# schematic.net
KiCad netlist of a schematic drawn in EasyEDA
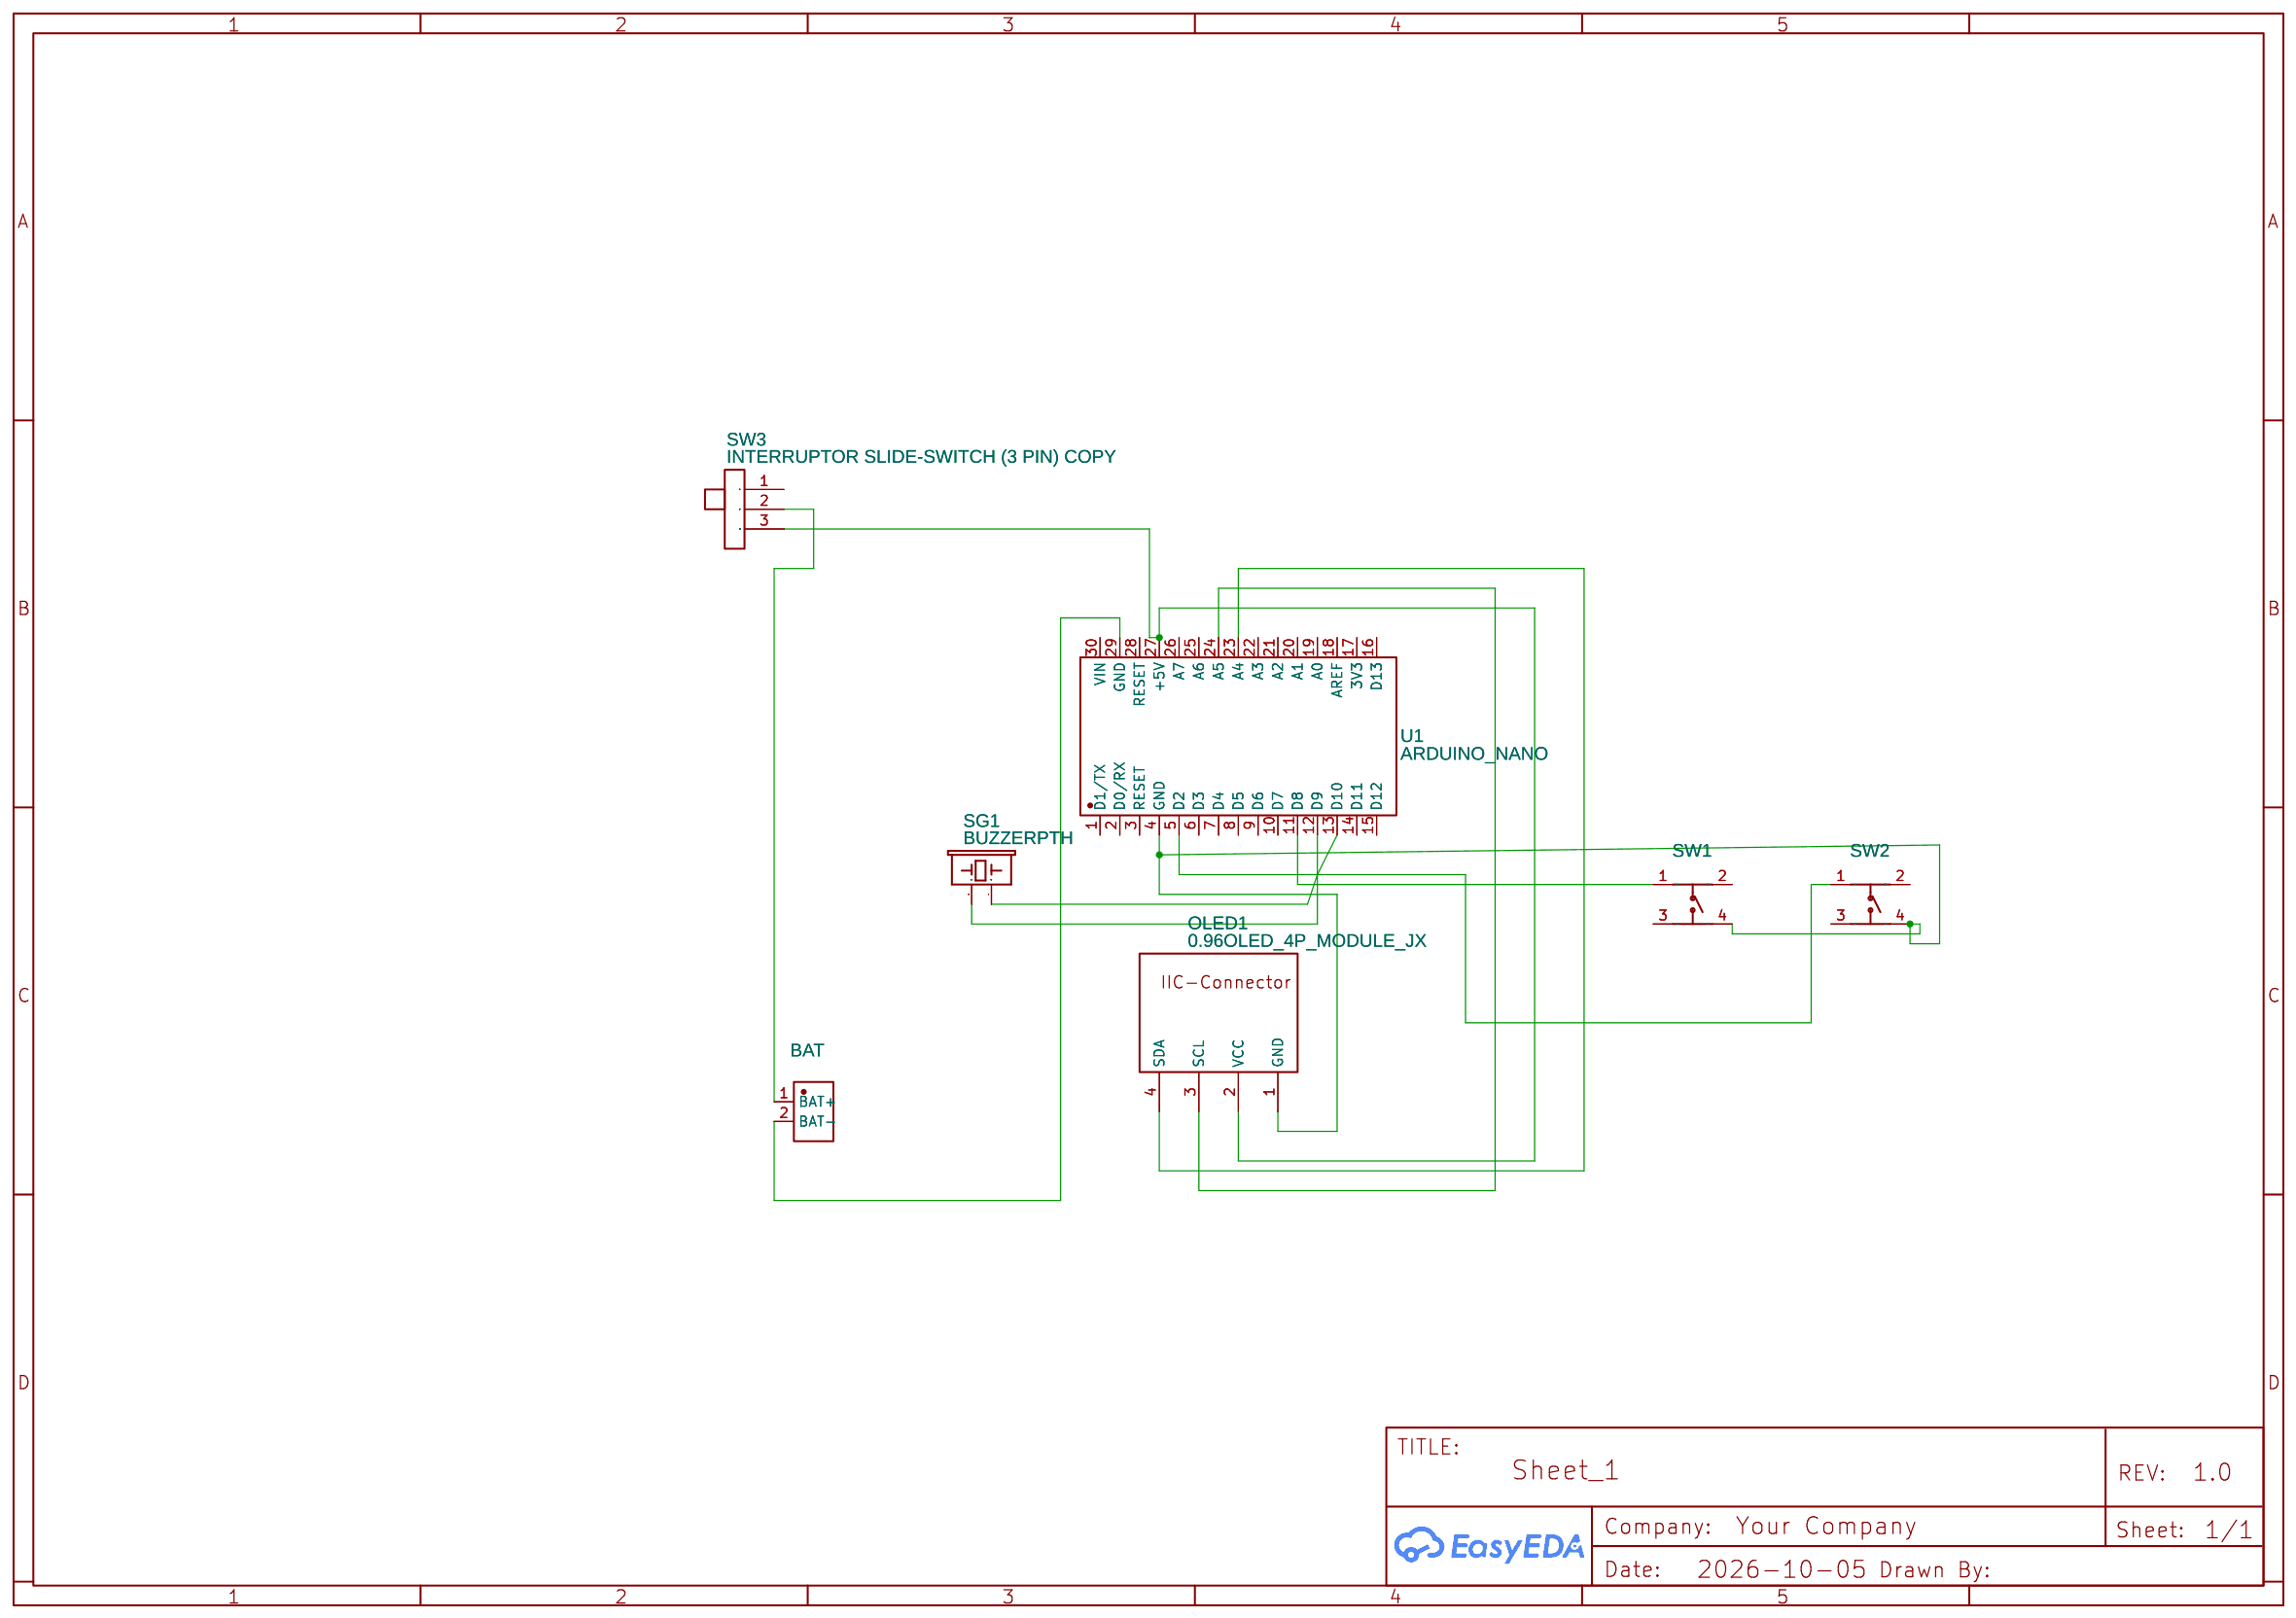
[diagram p0: schematic sheet]

(export (version "E")
  (design (tool "Eeschema 10.0.6"))
  (components
    (comp (ref "BAT")
      (value "880-70-002-10-001101")
      (fields (field (name "Manufacturer") "Preci-Dip"))
      (libsource (lib "") (part "880-70-002-10-001101"))
    )
    (comp (ref "OLED1") (value "0.96OLED_4P_MODULE_JX") (libsource (lib "") (part "0.96OLED_4P_MODULE_JX")))
    (comp (ref "SG1") (value "BUZZERPTH") (libsource (lib "") (part "BUZZERPTH")))
    (comp (ref "SW1")
      (value "SW1")
      (fields (field (name "Manufacturer Part") "Buttontact-6x6mm"))
      (libsource (lib "") (part "BUTTONTACT-6X6MM"))
    )
    (comp (ref "SW2")
      (value "SW2")
      (fields (field (name "Manufacturer Part") "Buttontact-6x6mm"))
      (libsource (lib "") (part "BUTTONTACT-6X6MM"))
    )
    (comp (ref "SW3")
      (value "INTERRUPTOR SLIDE-SWITCH (3 PIN) COPY")
      (fields (field (name "Manufacturer") "A+A Technology Co.,Ltd"))
      (libsource (lib "") (part "INTERRUPTOR SLIDE-SWITCH (3 PIN) COPY"))
    )
    (comp (ref "U1") (value "ARDUINO_NANO") (libsource (lib "") (part "ARDUINO_NANO")))
  )
  (nets
    (net (code "1") (name "Net-(BAT-BAT+)") (class "Default")
      (node (ref "BAT") (pin "1") (pinfunction "BAT+_1") (pintype "unspecified"))
      (node (ref "SW3") (pin "2") (pinfunction "2_2") (pintype "unspecified"))
    )
    (net (code "2") (name "Net-(BAT-BAT-)") (class "Default")
      (node (ref "BAT") (pin "2") (pinfunction "BAT-_2") (pintype "unspecified"))
      (node (ref "U1") (pin "29") (pinfunction "GND_29") (pintype "unspecified"))
    )
    (net (code "3") (name "Net-(OLED1-GND)") (class "Default")
      (node (ref "OLED1") (pin "1") (pinfunction "GND_1") (pintype "unspecified"))
      (node (ref "SW1") (pin "4") (pinfunction "D_4") (pintype "unspecified"))
      (node (ref "SW2") (pin "4") (pinfunction "D_4") (pintype "unspecified"))
      (node (ref "U1") (pin "4") (pinfunction "GND_4") (pintype "unspecified"))
    )
    (net (code "4") (name "Net-(OLED1-SCL)") (class "Default")
      (node (ref "OLED1") (pin "3") (pinfunction "SCL_3") (pintype "unspecified"))
      (node (ref "U1") (pin "24") (pinfunction "A5_24") (pintype "unspecified"))
    )
    (net (code "5") (name "Net-(OLED1-SDA)") (class "Default")
      (node (ref "OLED1") (pin "4") (pinfunction "SDA_4") (pintype "unspecified"))
      (node (ref "U1") (pin "23") (pinfunction "A4_23") (pintype "unspecified"))
    )
    (net (code "6") (name "Net-(OLED1-VCC)") (class "Default")
      (node (ref "OLED1") (pin "2") (pinfunction "VCC_2") (pintype "unspecified"))
      (node (ref "SW3") (pin "3") (pinfunction "3_3") (pintype "unspecified"))
      (node (ref "U1") (pin "27") (pinfunction "+5V_27") (pintype "unspecified"))
    )
    (net (code "7") (name "Net-(SG1-1)") (class "Default")
      (node (ref "SG1") (pin "+") (pinfunction "1_+") (pintype "unspecified"))
      (node (ref "U1") (pin "12") (pinfunction "D9_12") (pintype "unspecified"))
    )
    (net (code "8") (name "Net-(SG1-2)") (class "Default")
      (node (ref "SG1") (pin "-") (pinfunction "2_-") (pintype "unspecified"))
      (node (ref "U1") (pin "13") (pinfunction "D10_13") (pintype "unspecified"))
    )
    (net (code "9") (name "Net-(SW1-A)") (class "Default")
      (node (ref "SW1") (pin "1") (pinfunction "A_1") (pintype "unspecified"))
      (node (ref "U1") (pin "11") (pinfunction "D8_11") (pintype "unspecified"))
    )
    (net (code "10") (name "Net-(SW2-A)") (class "Default")
      (node (ref "SW2") (pin "1") (pinfunction "A_1") (pintype "unspecified"))
      (node (ref "U1") (pin "5") (pinfunction "D2_5") (pintype "unspecified"))
    )
    (net (code "11") (name "unconnected-(SW1-B-Pad2)") (class "Default")
      (node (ref "SW1") (pin "2") (pinfunction "B_2") (pintype "unspecified"))
    )
    (net (code "12") (name "unconnected-(SW1-C-Pad3)") (class "Default")
      (node (ref "SW1") (pin "3") (pinfunction "C_3") (pintype "unspecified"))
    )
    (net (code "13") (name "unconnected-(SW2-B-Pad2)") (class "Default")
      (node (ref "SW2") (pin "2") (pinfunction "B_2") (pintype "unspecified"))
    )
    (net (code "14") (name "unconnected-(SW2-C-Pad3)") (class "Default")
      (node (ref "SW2") (pin "3") (pinfunction "C_3") (pintype "unspecified"))
    )
    (net (code "15") (name "unconnected-(SW3-Pad1)") (class "Default")
      (node (ref "SW3") (pin "1") (pinfunction "1_1") (pintype "unspecified"))
    )
    (net (code "16") (name "unconnected-(U1-3V3-Pad17)") (class "Default")
      (node (ref "U1") (pin "17") (pinfunction "3V3_17") (pintype "unspecified"))
    )
    (net (code "17") (name "unconnected-(U1-A0-Pad19)") (class "Default")
      (node (ref "U1") (pin "19") (pinfunction "A0_19") (pintype "unspecified"))
    )
    (net (code "18") (name "unconnected-(U1-A1-Pad20)") (class "Default")
      (node (ref "U1") (pin "20") (pinfunction "A1_20") (pintype "unspecified"))
    )
    (net (code "19") (name "unconnected-(U1-A2-Pad21)") (class "Default")
      (node (ref "U1") (pin "21") (pinfunction "A2_21") (pintype "unspecified"))
    )
    (net (code "20") (name "unconnected-(U1-A3-Pad22)") (class "Default")
      (node (ref "U1") (pin "22") (pinfunction "A3_22") (pintype "unspecified"))
    )
    (net (code "21") (name "unconnected-(U1-A6-Pad25)") (class "Default")
      (node (ref "U1") (pin "25") (pinfunction "A6_25") (pintype "unspecified"))
    )
    (net (code "22") (name "unconnected-(U1-A7-Pad26)") (class "Default")
      (node (ref "U1") (pin "26") (pinfunction "A7_26") (pintype "unspecified"))
    )
    (net (code "23") (name "unconnected-(U1-AREF-Pad18)") (class "Default")
      (node (ref "U1") (pin "18") (pinfunction "AREF_18") (pintype "unspecified"))
    )
    (net (code "24") (name "unconnected-(U1-D0{slash}RX-Pad2)") (class "Default")
      (node (ref "U1") (pin "2") (pinfunction "D0/RX_2") (pintype "unspecified"))
    )
    (net (code "25") (name "unconnected-(U1-D1{slash}TX-Pad1)") (class "Default")
      (node (ref "U1") (pin "1") (pinfunction "D1/TX_1") (pintype "unspecified"))
    )
    (net (code "26") (name "unconnected-(U1-D3-Pad6)") (class "Default")
      (node (ref "U1") (pin "6") (pinfunction "D3_6") (pintype "unspecified"))
    )
    (net (code "27") (name "unconnected-(U1-D4-Pad7)") (class "Default")
      (node (ref "U1") (pin "7") (pinfunction "D4_7") (pintype "unspecified"))
    )
    (net (code "28") (name "unconnected-(U1-D5-Pad8)") (class "Default")
      (node (ref "U1") (pin "8") (pinfunction "D5_8") (pintype "unspecified"))
    )
    (net (code "29") (name "unconnected-(U1-D6-Pad9)") (class "Default")
      (node (ref "U1") (pin "9") (pinfunction "D6_9") (pintype "unspecified"))
    )
    (net (code "30") (name "unconnected-(U1-D7-Pad10)") (class "Default")
      (node (ref "U1") (pin "10") (pinfunction "D7_10") (pintype "unspecified"))
    )
    (net (code "31") (name "unconnected-(U1-D11-Pad14)") (class "Default")
      (node (ref "U1") (pin "14") (pinfunction "D11_14") (pintype "unspecified"))
    )
    (net (code "32") (name "unconnected-(U1-D12-Pad15)") (class "Default")
      (node (ref "U1") (pin "15") (pinfunction "D12_15") (pintype "unspecified"))
    )
    (net (code "33") (name "unconnected-(U1-D13-Pad16)") (class "Default")
      (node (ref "U1") (pin "16") (pinfunction "D13_16") (pintype "unspecified"))
    )
    (net (code "34") (name "unconnected-(U1-RESET-Pad3)") (class "Default")
      (node (ref "U1") (pin "3") (pinfunction "RESET_3") (pintype "unspecified"))
    )
    (net (code "35") (name "unconnected-(U1-RESET-Pad28)") (class "Default")
      (node (ref "U1") (pin "28") (pinfunction "RESET_28") (pintype "unspecified"))
    )
    (net (code "36") (name "unconnected-(U1-VIN-Pad30)") (class "Default")
      (node (ref "U1") (pin "30") (pinfunction "VIN_30") (pintype "unspecified"))
    )
  )
)
